# Logica_ADC.net
KiCad netlist of a schematic drawn in Altium Designer
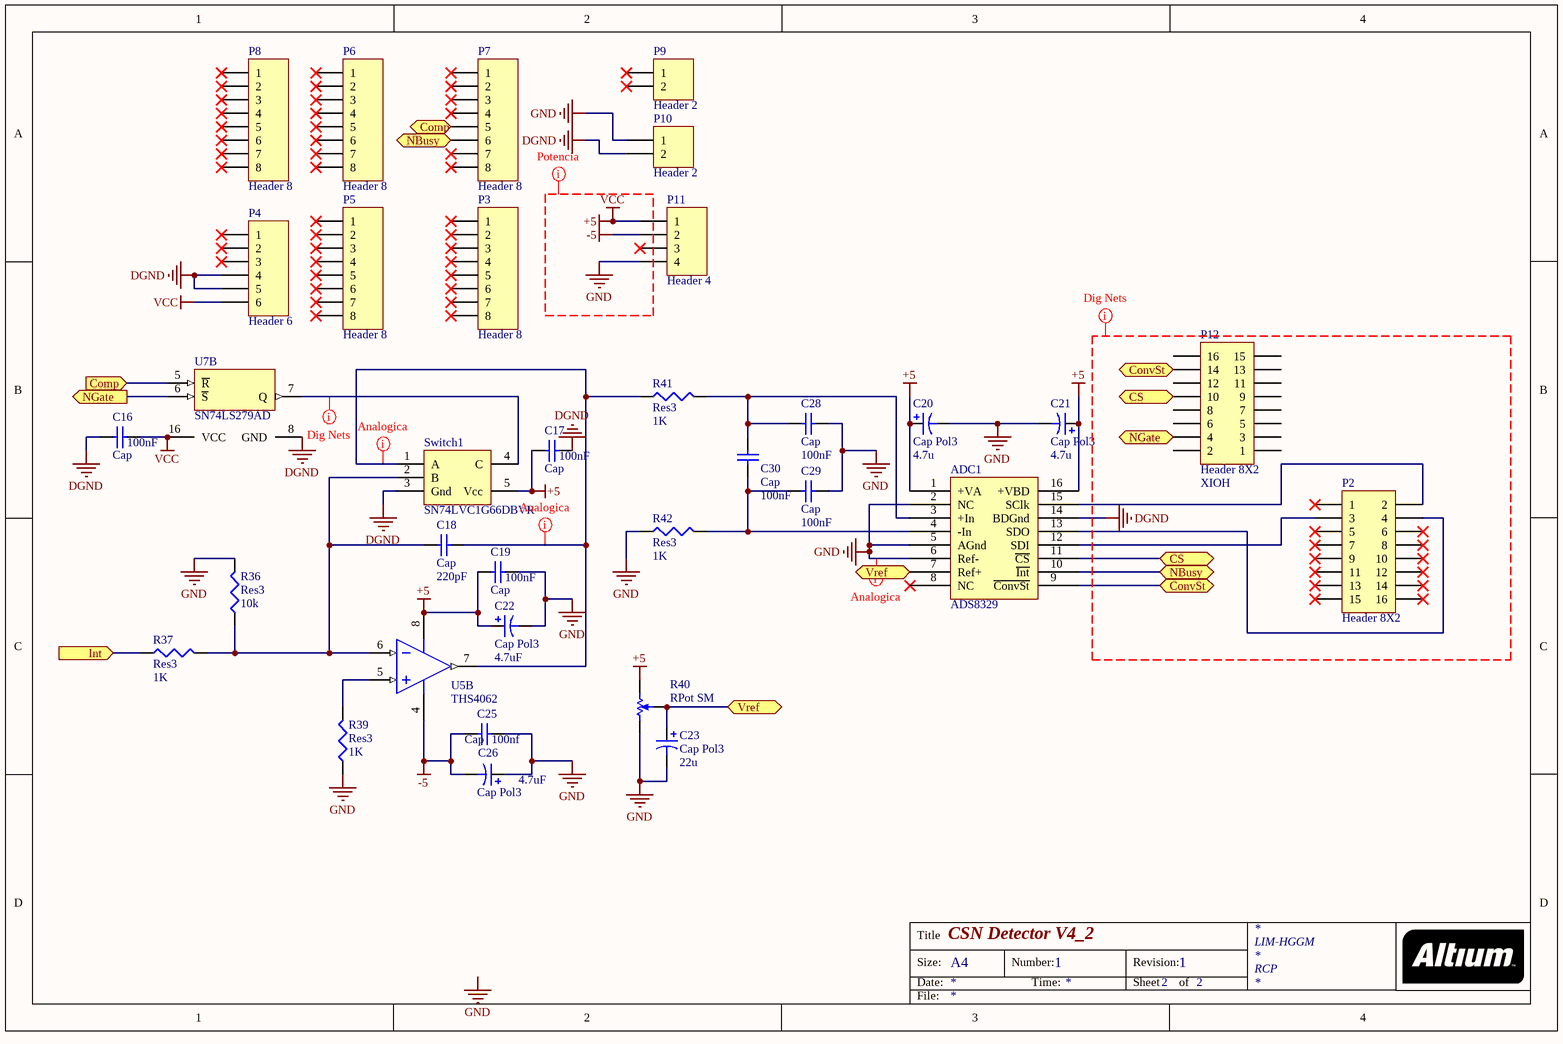
[diagram p0: Logica_ADC.SchDoc]

(export (version "E")
  (design (tool "Eeschema 10.0.6"))
  (components
    (comp (ref "ADC1")
      (value "ADS8329")
      (footprint "PW-R-PDSO-G16")
      (libsource (lib "Int_Lib1") (part "ADS8329"))
    )
    (comp (ref "C16")
      (value "Cap")
      (footprint "6-0805_N")
      (description "Capacitor")
      (fields (field (name "ALTIUM_VALUE") "100nF") (field (name "PUBLISHER") "Altium Limited"))
      (libsource (lib "Miscellaneous Devices") (part "Cap"))
    )
    (comp (ref "C17")
      (value "Cap")
      (footprint "6-0805_N")
      (description "Capacitor")
      (fields (field (name "ALTIUM_VALUE") "100nF") (field (name "PUBLISHER") "Altium Limited"))
      (libsource (lib "Miscellaneous Devices") (part "Cap"))
    )
    (comp (ref "C18")
      (value "Cap")
      (footprint "6-0805_N")
      (description "Capacitor")
      (fields (field (name "ALTIUM_VALUE") "220pF") (field (name "PUBLISHER") "Altium Limited"))
      (libsource (lib "Miscellaneous Devices") (part "Cap"))
    )
    (comp (ref "C19")
      (value "Cap")
      (footprint "6-0805_N")
      (description "Capacitor")
      (fields (field (name "ALTIUM_VALUE") "100nF") (field (name "PUBLISHER") "Altium Limited"))
      (libsource (lib "Miscellaneous Devices") (part "Cap"))
    )
    (comp (ref "C20")
      (value "Cap Pol3")
      (footprint "6-0805_N")
      (description "Polarized Capacitor (Surface Mount)")
      (fields (field (name "ALTIUM_VALUE") "4.7u") (field (name "PUBLISHER") "Altium Limited"))
      (libsource (lib "Miscellaneous Devices") (part "Cap Pol3"))
    )
    (comp (ref "C21")
      (value "Cap Pol3")
      (footprint "6-0805_N")
      (description "Polarized Capacitor (Surface Mount)")
      (fields (field (name "ALTIUM_VALUE") "4.7u") (field (name "PUBLISHER") "Altium Limited"))
      (libsource (lib "Miscellaneous Devices") (part "Cap Pol3"))
    )
    (comp (ref "C22")
      (value "Cap Pol3")
      (footprint "6-0805_N")
      (description "Polarized Capacitor (Surface Mount)")
      (fields (field (name "ALTIUM_VALUE") "4.7uF") (field (name "PUBLISHER") "Altium Limited"))
      (libsource (lib "Miscellaneous Devices") (part "Cap Pol3"))
    )
    (comp (ref "C23")
      (value "Cap Pol3")
      (footprint "6-0805_N")
      (description "Polarized Capacitor (Surface Mount)")
      (fields (field (name "ALTIUM_VALUE") "22u") (field (name "PUBLISHER") "Altium Limited"))
      (libsource (lib "Miscellaneous Devices") (part "Cap Pol3"))
    )
    (comp (ref "C25")
      (value "Cap")
      (footprint "6-0805_N")
      (description "Capacitor")
      (fields (field (name "ALTIUM_VALUE") "100nf") (field (name "PUBLISHER") "Altium Limited"))
      (libsource (lib "Miscellaneous Devices") (part "Cap"))
    )
    (comp (ref "C26")
      (value "Cap Pol3")
      (footprint "6-0805_N")
      (description "Polarized Capacitor (Surface Mount)")
      (fields (field (name "ALTIUM_VALUE") "4.7uF") (field (name "PUBLISHER") "Altium Limited"))
      (libsource (lib "Miscellaneous Devices") (part "Cap Pol3"))
    )
    (comp (ref "C28")
      (value "Cap")
      (footprint "6-0805_N")
      (description "Capacitor")
      (fields (field (name "ALTIUM_VALUE") "100nF") (field (name "PUBLISHER") "Altium Limited"))
      (libsource (lib "Miscellaneous Devices") (part "Cap"))
    )
    (comp (ref "C29")
      (value "Cap")
      (footprint "6-0805_N")
      (description "Capacitor")
      (fields (field (name "ALTIUM_VALUE") "100nF") (field (name "PUBLISHER") "Altium Limited"))
      (libsource (lib "Miscellaneous Devices") (part "Cap"))
    )
    (comp (ref "C30")
      (value "Cap")
      (footprint "6-0805_N")
      (description "Capacitor")
      (fields (field (name "ALTIUM_VALUE") "100nF") (field (name "PUBLISHER") "Altium Limited"))
      (libsource (lib "Miscellaneous Devices") (part "Cap"))
    )
    (comp (ref "P2")
      (value "Header 8X2")
      (footprint "HDR2X8")
      (description "Header, 8-Pin, Dual row")
      (fields (field (name "PUBLISHER") "Altium Limited"))
      (libsource (lib "") (part "Header 8X2_1"))
    )
    (comp (ref "P3")
      (value "Header 8")
      (footprint "HDR1X8")
      (description "Header, 8-Pin")
      (fields (field (name "PUBLISHER") "Altium Limited"))
      (libsource (lib "Miscellaneous Connectors") (part "Header 8"))
    )
    (comp (ref "P4")
      (value "Header 6")
      (footprint "HDR1X6")
      (description "Header, 6-Pin")
      (fields (field (name "PUBLISHER") "Altium Limited"))
      (libsource (lib "Miscellaneous Connectors") (part "Header 6"))
    )
    (comp (ref "P5")
      (value "Header 8")
      (footprint "HDR1X8")
      (description "Header, 8-Pin")
      (fields (field (name "PUBLISHER") "Altium Limited"))
      (libsource (lib "Miscellaneous Connectors") (part "Header 8"))
    )
    (comp (ref "P6")
      (value "Header 8")
      (footprint "HDR1X8")
      (description "Header, 8-Pin")
      (fields (field (name "PUBLISHER") "Altium Limited"))
      (libsource (lib "Miscellaneous Connectors") (part "Header 8"))
    )
    (comp (ref "P7")
      (value "Header 8")
      (footprint "HDR1X8")
      (description "Header, 8-Pin")
      (fields (field (name "PUBLISHER") "Altium Limited"))
      (libsource (lib "Miscellaneous Connectors") (part "Header 8"))
    )
    (comp (ref "P8")
      (value "Header 8")
      (footprint "HDR1X8")
      (description "Header, 8-Pin")
      (fields (field (name "PUBLISHER") "Altium Limited"))
      (libsource (lib "Miscellaneous Connectors") (part "Header 8"))
    )
    (comp (ref "P9")
      (value "Header 2")
      (footprint "HDR1X2")
      (description "Header, 2-Pin")
      (fields (field (name "PUBLISHER") "Altium Limited"))
      (libsource (lib "Miscellaneous Connectors") (part "Header 2"))
    )
    (comp (ref "P10")
      (value "Header 2")
      (footprint "HDR1X2")
      (description "Header, 2-Pin")
      (fields (field (name "PUBLISHER") "Altium Limited"))
      (libsource (lib "Miscellaneous Connectors") (part "Header 2"))
    )
    (comp (ref "P11")
      (value "Header 4")
      (footprint "HDR1X4")
      (description "Header, 4-Pin")
      (fields (field (name "PUBLISHER") "Altium Limited"))
      (libsource (lib "Miscellaneous Connectors") (part "Header 4"))
    )
    (comp (ref "P12")
      (value "Header 8X2")
      (footprint "HDR2X8")
      (description "Header, 8-Pin, Dual row")
      (fields (field (name "CON_ARDUINO") "XIOH") (field (name "PUBLISHER") "Altium Limited"))
      (libsource (lib "Miscellaneous Connectors") (part "Header 8X2"))
    )
    (comp (ref "R36")
      (value "Res3")
      (footprint "6-0805_N")
      (description "Resistor")
      (fields (field (name "ALTIUM_VALUE") "10k") (field (name "PUBLISHER") "Altium Limited"))
      (libsource (lib "Miscellaneous Devices") (part "Res3"))
    )
    (comp (ref "R37")
      (value "Res3")
      (footprint "6-0805_N")
      (description "Resistor")
      (fields (field (name "ALTIUM_VALUE") "1K") (field (name "PUBLISHER") "Altium Limited"))
      (libsource (lib "Miscellaneous Devices") (part "Res3"))
    )
    (comp (ref "R39")
      (value "Res3")
      (footprint "6-0805_N")
      (description "Resistor")
      (fields (field (name "ALTIUM_VALUE") "1K") (field (name "PUBLISHER") "Altium Limited"))
      (libsource (lib "Miscellaneous Devices") (part "Res3"))
    )
    (comp (ref "R40")
      (value "RPot SM")
      (footprint "POT4MM-2")
      (description "Square Trimming Potentiometer")
      (fields (field (name "PUBLISHER") "Altium Limited"))
      (libsource (lib "Miscellaneous Devices") (part "RPot SM"))
    )
    (comp (ref "R41")
      (value "Res3")
      (footprint "6-0805_N")
      (description "Resistor")
      (fields (field (name "ALTIUM_VALUE") "1K") (field (name "PUBLISHER") "Altium Limited"))
      (libsource (lib "Miscellaneous Devices") (part "Res3"))
    )
    (comp (ref "R42")
      (value "Res3")
      (footprint "6-0805_N")
      (description "Resistor")
      (fields (field (name "ALTIUM_VALUE") "1K") (field (name "PUBLISHER") "Altium Limited"))
      (libsource (lib "Miscellaneous Devices") (part "Res3"))
    )
    (comp (ref "Switch1")
      (value "SN74LVC1G66DBVR")
      (footprint "SOT23-5_N")
      (libsource (lib "Integrated_Library1") (part "SN74LVC1G66DBVR"))
    )
    (comp (ref "U5")
      (value "THS4062")
      (footprint "S8_N")
      (description "Low Cost Dual Video Amplifier")
      (fields (field (name "PUBLISHER") "Altium Limited"))
      (libsource (lib "LT Video Amplifier") (part "LT1253CS8"))
    )
    (comp (ref "U7")
      (value "SN74LS279AD")
      (footprint "D016_N")
      (description "Quadruple S-R Latches")
      (fields (field (name "PUBLISHER") "Altium Limited"))
      (libsource (lib "TI Logic Latch") (part "SN74LS279AD"))
    )
  )
  (nets
    (net (code "1") (name "+5") (class "Default")
      (node (ref "ADC1") (pin "1") (pinfunction "+VA_1") (pintype "passive"))
      (node (ref "ADC1") (pin "16") (pinfunction "+VBD_16") (pintype "passive"))
      (node (ref "C16") (pin "1") (pinfunction "1_1") (pintype "passive"))
      (node (ref "C17") (pin "2") (pinfunction "2_2") (pintype "passive"))
      (node (ref "C19") (pin "2") (pinfunction "2_2") (pintype "passive"))
      (node (ref "C20") (pin "1") (pinfunction "1_1") (pintype "passive"))
      (node (ref "C21") (pin "1") (pinfunction "1_1") (pintype "passive"))
      (node (ref "C22") (pin "1") (pinfunction "1_1") (pintype "passive"))
      (node (ref "P11") (pin "1") (pinfunction "1_1") (pintype "passive"))
      (node (ref "P4") (pin "6") (pinfunction "6_6") (pintype "passive"))
      (node (ref "R40") (pin "CW") (pinfunction "+_CW") (pintype "passive"))
      (node (ref "Switch1") (pin "5") (pinfunction "Vcc_5") (pintype "passive"))
      (node (ref "U5") (pin "8") (pinfunction "V+_8") (pintype "power_in"))
      (node (ref "U7") (pin "16") (pinfunction "VCC_16") (pintype "power_in"))
    )
    (net (code "2") (name "-5") (class "Default")
      (node (ref "C25") (pin "1") (pinfunction "1_1") (pintype "passive"))
      (node (ref "C26") (pin "2") (pinfunction "2_2") (pintype "passive"))
      (node (ref "P11") (pin "2") (pinfunction "2_2") (pintype "passive"))
      (node (ref "U5") (pin "4") (pinfunction "V-_4") (pintype "power_in"))
    )
    (net (code "3") (name "/CS") (class "Default")
      (node (ref "ADC1") (pin "11") (pinfunction "~{CS}_11") (pintype "passive"))
      (node (ref "P12") (pin "10") (pinfunction "10_10") (pintype "passive"))
    )
    (net (code "4") (name "/Comp") (class "Default")
      (node (ref "P7") (pin "5") (pinfunction "5_5") (pintype "passive"))
      (node (ref "U7") (pin "5") (pinfunction "~{R}_5") (pintype "input"))
    )
    (net (code "5") (name "/ConvSt") (class "Default")
      (node (ref "ADC1") (pin "9") (pinfunction "~{ConvSt}_9") (pintype "passive"))
      (node (ref "P12") (pin "14") (pinfunction "14_14") (pintype "passive"))
    )
    (net (code "6") (name "/Int") (class "Default")
      (node (ref "R37") (pin "1") (pinfunction "1_1") (pintype "passive"))
    )
    (net (code "7") (name "/NBusy") (class "Default")
      (node (ref "ADC1") (pin "10") (pinfunction "~{Int}_10") (pintype "passive"))
      (node (ref "P7") (pin "6") (pinfunction "6_6") (pintype "passive"))
    )
    (net (code "8") (name "/NGate") (class "Default")
      (node (ref "P12") (pin "4") (pinfunction "4_4") (pintype "passive"))
      (node (ref "U7") (pin "6") (pinfunction "~{S}_6") (pintype "input"))
    )
    (net (code "9") (name "/Vref") (class "Default")
      (node (ref "ADC1") (pin "7") (pinfunction "Ref+_7") (pintype "passive"))
      (node (ref "C23") (pin "1") (pinfunction "1_1") (pintype "passive"))
      (node (ref "R40") (pin "W") (pinfunction "W_W") (pintype "passive"))
    )
    (net (code "10") (name "DGND") (class "Default")
      (node (ref "ADC1") (pin "14") (pinfunction "BDGnd_14") (pintype "passive"))
      (node (ref "ADC1") (pin "2") (pinfunction "NC_2") (pintype "passive"))
      (node (ref "ADC1") (pin "5") (pinfunction "AGnd_5") (pintype "passive"))
      (node (ref "ADC1") (pin "6") (pinfunction "Ref-_6") (pintype "passive"))
      (node (ref "C16") (pin "2") (pinfunction "2_2") (pintype "passive"))
      (node (ref "C17") (pin "1") (pinfunction "1_1") (pintype "passive"))
      (node (ref "C19") (pin "1") (pinfunction "1_1") (pintype "passive"))
      (node (ref "C20") (pin "2") (pinfunction "2_2") (pintype "passive"))
      (node (ref "C21") (pin "2") (pinfunction "2_2") (pintype "passive"))
      (node (ref "C22") (pin "2") (pinfunction "2_2") (pintype "passive"))
      (node (ref "C23") (pin "2") (pinfunction "2_2") (pintype "passive"))
      (node (ref "C25") (pin "2") (pinfunction "2_2") (pintype "passive"))
      (node (ref "C26") (pin "1") (pinfunction "1_1") (pintype "passive"))
      (node (ref "C28") (pin "1") (pinfunction "1_1") (pintype "passive"))
      (node (ref "C29") (pin "1") (pinfunction "1_1") (pintype "passive"))
      (node (ref "P10") (pin "1") (pinfunction "1_1") (pintype "passive"))
      (node (ref "P10") (pin "2") (pinfunction "2_2") (pintype "passive"))
      (node (ref "P11") (pin "4") (pinfunction "4_4") (pintype "passive"))
      (node (ref "P4") (pin "4") (pinfunction "4_4") (pintype "passive"))
      (node (ref "P4") (pin "5") (pinfunction "5_5") (pintype "passive"))
      (node (ref "R36") (pin "2") (pinfunction "2_2") (pintype "passive"))
      (node (ref "R39") (pin "1") (pinfunction "1_1") (pintype "passive"))
      (node (ref "R40") (pin "CCW") (pinfunction "-_CCW") (pintype "passive"))
      (node (ref "R42") (pin "1") (pinfunction "1_1") (pintype "passive"))
      (node (ref "Switch1") (pin "3") (pinfunction "Gnd_3") (pintype "passive"))
      (node (ref "U7") (pin "8") (pinfunction "GND_8") (pintype "power_in"))
    )
    (net (code "11") (name "Net-(ADC1-+In)") (class "Default")
      (node (ref "ADC1") (pin "3") (pinfunction "+In_3") (pintype "passive"))
      (node (ref "C28") (pin "2") (pinfunction "2_2") (pintype "passive"))
      (node (ref "C30") (pin "2") (pinfunction "2_2") (pintype "passive"))
      (node (ref "R41") (pin "2") (pinfunction "2_2") (pintype "passive"))
    )
    (net (code "12") (name "Net-(ADC1--In)") (class "Default")
      (node (ref "ADC1") (pin "4") (pinfunction "-In_4") (pintype "passive"))
      (node (ref "C29") (pin "2") (pinfunction "2_2") (pintype "passive"))
      (node (ref "C30") (pin "1") (pinfunction "1_1") (pintype "passive"))
      (node (ref "R42") (pin "2") (pinfunction "2_2") (pintype "passive"))
    )
    (net (code "13") (name "Net-(ADC1-SClk)") (class "Default")
      (node (ref "ADC1") (pin "15") (pinfunction "SClk_15") (pintype "passive"))
      (node (ref "P2") (pin "2") (pinfunction "2_2") (pintype "passive"))
    )
    (net (code "14") (name "Net-(ADC1-SDI)") (class "Default")
      (node (ref "ADC1") (pin "12") (pinfunction "SDI_12") (pintype "passive"))
      (node (ref "P2") (pin "3") (pinfunction "3_3") (pintype "passive"))
    )
    (net (code "15") (name "Net-(ADC1-SDO)") (class "Default")
      (node (ref "ADC1") (pin "13") (pinfunction "SDO_13") (pintype "passive"))
      (node (ref "P2") (pin "4") (pinfunction "4_4") (pintype "passive"))
    )
    (net (code "16") (name "Net-(Switch1-A)") (class "Default")
      (node (ref "C18") (pin "2") (pinfunction "2_2") (pintype "passive"))
      (node (ref "R41") (pin "1") (pinfunction "1_1") (pintype "passive"))
      (node (ref "Switch1") (pin "1") (pinfunction "A_1") (pintype "passive"))
      (node (ref "U5") (pin "7") (pinfunction "OUT_7") (pintype "output"))
    )
    (net (code "17") (name "Net-(Switch1-B)") (class "Default")
      (node (ref "C18") (pin "1") (pinfunction "1_1") (pintype "passive"))
      (node (ref "R36") (pin "1") (pinfunction "1_1") (pintype "passive"))
      (node (ref "R37") (pin "2") (pinfunction "2_2") (pintype "passive"))
      (node (ref "Switch1") (pin "2") (pinfunction "B_2") (pintype "passive"))
      (node (ref "U5") (pin "6") (pinfunction "IN-_6") (pintype "input"))
    )
    (net (code "18") (name "Net-(Switch1-C)") (class "Default")
      (node (ref "Switch1") (pin "4") (pinfunction "C_4") (pintype "passive"))
      (node (ref "U7") (pin "7") (pinfunction "Q_7") (pintype "output"))
    )
    (net (code "19") (name "Net-(U5B-IN+)") (class "Default")
      (node (ref "R39") (pin "2") (pinfunction "2_2") (pintype "passive"))
      (node (ref "U5") (pin "5") (pinfunction "IN+_5") (pintype "input"))
    )
    (net (code "20") (name "unconnected-(ADC1-NC-Pad8)") (class "Default")
      (node (ref "ADC1") (pin "8") (pinfunction "NC_8") (pintype "passive+no_connect"))
    )
    (net (code "21") (name "unconnected-(P2-Pad1)") (class "Default")
      (node (ref "P2") (pin "1") (pinfunction "1_1") (pintype "passive+no_connect"))
    )
    (net (code "22") (name "unconnected-(P2-Pad5)") (class "Default")
      (node (ref "P2") (pin "5") (pinfunction "5_5") (pintype "passive+no_connect"))
    )
    (net (code "23") (name "unconnected-(P2-Pad6)") (class "Default")
      (node (ref "P2") (pin "6") (pinfunction "6_6") (pintype "passive+no_connect"))
    )
    (net (code "24") (name "unconnected-(P2-Pad7)") (class "Default")
      (node (ref "P2") (pin "7") (pinfunction "7_7") (pintype "passive+no_connect"))
    )
    (net (code "25") (name "unconnected-(P2-Pad8)") (class "Default")
      (node (ref "P2") (pin "8") (pinfunction "8_8") (pintype "passive+no_connect"))
    )
    (net (code "26") (name "unconnected-(P2-Pad9)") (class "Default")
      (node (ref "P2") (pin "9") (pinfunction "9_9") (pintype "passive+no_connect"))
    )
    (net (code "27") (name "unconnected-(P2-Pad10)") (class "Default")
      (node (ref "P2") (pin "10") (pinfunction "10_10") (pintype "passive+no_connect"))
    )
    (net (code "28") (name "unconnected-(P2-Pad11)") (class "Default")
      (node (ref "P2") (pin "11") (pinfunction "11_11") (pintype "passive+no_connect"))
    )
    (net (code "29") (name "unconnected-(P2-Pad12)") (class "Default")
      (node (ref "P2") (pin "12") (pinfunction "12_12") (pintype "passive+no_connect"))
    )
    (net (code "30") (name "unconnected-(P2-Pad13)") (class "Default")
      (node (ref "P2") (pin "13") (pinfunction "13_13") (pintype "passive+no_connect"))
    )
    (net (code "31") (name "unconnected-(P2-Pad14)") (class "Default")
      (node (ref "P2") (pin "14") (pinfunction "14_14") (pintype "passive+no_connect"))
    )
    (net (code "32") (name "unconnected-(P2-Pad15)") (class "Default")
      (node (ref "P2") (pin "15") (pinfunction "15_15") (pintype "passive+no_connect"))
    )
    (net (code "33") (name "unconnected-(P2-Pad16)") (class "Default")
      (node (ref "P2") (pin "16") (pinfunction "16_16") (pintype "passive+no_connect"))
    )
    (net (code "34") (name "unconnected-(P3-Pad1)") (class "Default")
      (node (ref "P3") (pin "1") (pinfunction "1_1") (pintype "passive+no_connect"))
    )
    (net (code "35") (name "unconnected-(P3-Pad2)") (class "Default")
      (node (ref "P3") (pin "2") (pinfunction "2_2") (pintype "passive+no_connect"))
    )
    (net (code "36") (name "unconnected-(P3-Pad3)") (class "Default")
      (node (ref "P3") (pin "3") (pinfunction "3_3") (pintype "passive+no_connect"))
    )
    (net (code "37") (name "unconnected-(P3-Pad4)") (class "Default")
      (node (ref "P3") (pin "4") (pinfunction "4_4") (pintype "passive+no_connect"))
    )
    (net (code "38") (name "unconnected-(P3-Pad5)") (class "Default")
      (node (ref "P3") (pin "5") (pinfunction "5_5") (pintype "passive+no_connect"))
    )
    (net (code "39") (name "unconnected-(P3-Pad6)") (class "Default")
      (node (ref "P3") (pin "6") (pinfunction "6_6") (pintype "passive+no_connect"))
    )
    (net (code "40") (name "unconnected-(P3-Pad7)") (class "Default")
      (node (ref "P3") (pin "7") (pinfunction "7_7") (pintype "passive+no_connect"))
    )
    (net (code "41") (name "unconnected-(P3-Pad8)") (class "Default")
      (node (ref "P3") (pin "8") (pinfunction "8_8") (pintype "passive+no_connect"))
    )
    (net (code "42") (name "unconnected-(P4-Pad1)") (class "Default")
      (node (ref "P4") (pin "1") (pinfunction "1_1") (pintype "passive+no_connect"))
    )
    (net (code "43") (name "unconnected-(P4-Pad2)") (class "Default")
      (node (ref "P4") (pin "2") (pinfunction "2_2") (pintype "passive+no_connect"))
    )
    (net (code "44") (name "unconnected-(P4-Pad3)") (class "Default")
      (node (ref "P4") (pin "3") (pinfunction "3_3") (pintype "passive+no_connect"))
    )
    (net (code "45") (name "unconnected-(P5-Pad1)") (class "Default")
      (node (ref "P5") (pin "1") (pinfunction "1_1") (pintype "passive+no_connect"))
    )
    (net (code "46") (name "unconnected-(P5-Pad2)") (class "Default")
      (node (ref "P5") (pin "2") (pinfunction "2_2") (pintype "passive+no_connect"))
    )
    (net (code "47") (name "unconnected-(P5-Pad3)") (class "Default")
      (node (ref "P5") (pin "3") (pinfunction "3_3") (pintype "passive+no_connect"))
    )
    (net (code "48") (name "unconnected-(P5-Pad4)") (class "Default")
      (node (ref "P5") (pin "4") (pinfunction "4_4") (pintype "passive+no_connect"))
    )
    (net (code "49") (name "unconnected-(P5-Pad5)") (class "Default")
      (node (ref "P5") (pin "5") (pinfunction "5_5") (pintype "passive+no_connect"))
    )
    (net (code "50") (name "unconnected-(P5-Pad6)") (class "Default")
      (node (ref "P5") (pin "6") (pinfunction "6_6") (pintype "passive+no_connect"))
    )
    (net (code "51") (name "unconnected-(P5-Pad7)") (class "Default")
      (node (ref "P5") (pin "7") (pinfunction "7_7") (pintype "passive+no_connect"))
    )
    (net (code "52") (name "unconnected-(P5-Pad8)") (class "Default")
      (node (ref "P5") (pin "8") (pinfunction "8_8") (pintype "passive+no_connect"))
    )
    (net (code "53") (name "unconnected-(P6-Pad1)") (class "Default")
      (node (ref "P6") (pin "1") (pinfunction "1_1") (pintype "passive+no_connect"))
    )
    (net (code "54") (name "unconnected-(P6-Pad2)") (class "Default")
      (node (ref "P6") (pin "2") (pinfunction "2_2") (pintype "passive+no_connect"))
    )
    (net (code "55") (name "unconnected-(P6-Pad3)") (class "Default")
      (node (ref "P6") (pin "3") (pinfunction "3_3") (pintype "passive+no_connect"))
    )
    (net (code "56") (name "unconnected-(P6-Pad4)") (class "Default")
      (node (ref "P6") (pin "4") (pinfunction "4_4") (pintype "passive+no_connect"))
    )
    (net (code "57") (name "unconnected-(P6-Pad5)") (class "Default")
      (node (ref "P6") (pin "5") (pinfunction "5_5") (pintype "passive+no_connect"))
    )
    (net (code "58") (name "unconnected-(P6-Pad6)") (class "Default")
      (node (ref "P6") (pin "6") (pinfunction "6_6") (pintype "passive+no_connect"))
    )
    (net (code "59") (name "unconnected-(P6-Pad7)") (class "Default")
      (node (ref "P6") (pin "7") (pinfunction "7_7") (pintype "passive+no_connect"))
    )
    (net (code "60") (name "unconnected-(P6-Pad8)") (class "Default")
      (node (ref "P6") (pin "8") (pinfunction "8_8") (pintype "passive+no_connect"))
    )
    (net (code "61") (name "unconnected-(P7-Pad1)") (class "Default")
      (node (ref "P7") (pin "1") (pinfunction "1_1") (pintype "passive+no_connect"))
    )
    (net (code "62") (name "unconnected-(P7-Pad2)") (class "Default")
      (node (ref "P7") (pin "2") (pinfunction "2_2") (pintype "passive+no_connect"))
    )
    (net (code "63") (name "unconnected-(P7-Pad3)") (class "Default")
      (node (ref "P7") (pin "3") (pinfunction "3_3") (pintype "passive+no_connect"))
    )
    (net (code "64") (name "unconnected-(P7-Pad4)") (class "Default")
      (node (ref "P7") (pin "4") (pinfunction "4_4") (pintype "passive+no_connect"))
    )
    (net (code "65") (name "unconnected-(P7-Pad7)") (class "Default")
      (node (ref "P7") (pin "7") (pinfunction "7_7") (pintype "passive+no_connect"))
    )
    (net (code "66") (name "unconnected-(P7-Pad8)") (class "Default")
      (node (ref "P7") (pin "8") (pinfunction "8_8") (pintype "passive+no_connect"))
    )
    (net (code "67") (name "unconnected-(P8-Pad1)") (class "Default")
      (node (ref "P8") (pin "1") (pinfunction "1_1") (pintype "passive+no_connect"))
    )
    (net (code "68") (name "unconnected-(P8-Pad2)") (class "Default")
      (node (ref "P8") (pin "2") (pinfunction "2_2") (pintype "passive+no_connect"))
    )
    (net (code "69") (name "unconnected-(P8-Pad3)") (class "Default")
      (node (ref "P8") (pin "3") (pinfunction "3_3") (pintype "passive+no_connect"))
    )
    (net (code "70") (name "unconnected-(P8-Pad4)") (class "Default")
      (node (ref "P8") (pin "4") (pinfunction "4_4") (pintype "passive+no_connect"))
    )
    (net (code "71") (name "unconnected-(P8-Pad5)") (class "Default")
      (node (ref "P8") (pin "5") (pinfunction "5_5") (pintype "passive+no_connect"))
    )
    (net (code "72") (name "unconnected-(P8-Pad6)") (class "Default")
      (node (ref "P8") (pin "6") (pinfunction "6_6") (pintype "passive+no_connect"))
    )
    (net (code "73") (name "unconnected-(P8-Pad7)") (class "Default")
      (node (ref "P8") (pin "7") (pinfunction "7_7") (pintype "passive+no_connect"))
    )
    (net (code "74") (name "unconnected-(P8-Pad8)") (class "Default")
      (node (ref "P8") (pin "8") (pinfunction "8_8") (pintype "passive+no_connect"))
    )
    (net (code "75") (name "unconnected-(P9-Pad1)") (class "Default")
      (node (ref "P9") (pin "1") (pinfunction "1_1") (pintype "passive+no_connect"))
    )
    (net (code "76") (name "unconnected-(P9-Pad2)") (class "Default")
      (node (ref "P9") (pin "2") (pinfunction "2_2") (pintype "passive+no_connect"))
    )
    (net (code "77") (name "unconnected-(P11-Pad3)") (class "Default")
      (node (ref "P11") (pin "3") (pinfunction "3_3") (pintype "passive+no_connect"))
    )
    (net (code "78") (name "unconnected-(P12-Pad1)") (class "Default")
      (node (ref "P12") (pin "1") (pinfunction "1_1") (pintype "passive"))
    )
    (net (code "79") (name "unconnected-(P12-Pad2)") (class "Default")
      (node (ref "P12") (pin "2") (pinfunction "2_2") (pintype "passive"))
    )
    (net (code "80") (name "unconnected-(P12-Pad3)") (class "Default")
      (node (ref "P12") (pin "3") (pinfunction "3_3") (pintype "passive"))
    )
    (net (code "81") (name "unconnected-(P12-Pad5)") (class "Default")
      (node (ref "P12") (pin "5") (pinfunction "5_5") (pintype "passive"))
    )
    (net (code "82") (name "unconnected-(P12-Pad6)") (class "Default")
      (node (ref "P12") (pin "6") (pinfunction "6_6") (pintype "passive"))
    )
    (net (code "83") (name "unconnected-(P12-Pad7)") (class "Default")
      (node (ref "P12") (pin "7") (pinfunction "7_7") (pintype "passive"))
    )
    (net (code "84") (name "unconnected-(P12-Pad8)") (class "Default")
      (node (ref "P12") (pin "8") (pinfunction "8_8") (pintype "passive"))
    )
    (net (code "85") (name "unconnected-(P12-Pad9)") (class "Default")
      (node (ref "P12") (pin "9") (pinfunction "9_9") (pintype "passive"))
    )
    (net (code "86") (name "unconnected-(P12-Pad11)") (class "Default")
      (node (ref "P12") (pin "11") (pinfunction "11_11") (pintype "passive"))
    )
    (net (code "87") (name "unconnected-(P12-Pad12)") (class "Default")
      (node (ref "P12") (pin "12") (pinfunction "12_12") (pintype "passive"))
    )
    (net (code "88") (name "unconnected-(P12-Pad13)") (class "Default")
      (node (ref "P12") (pin "13") (pinfunction "13_13") (pintype "passive"))
    )
    (net (code "89") (name "unconnected-(P12-Pad15)") (class "Default")
      (node (ref "P12") (pin "15") (pinfunction "15_15") (pintype "passive"))
    )
    (net (code "90") (name "unconnected-(P12-Pad16)") (class "Default")
      (node (ref "P12") (pin "16") (pinfunction "16_16") (pintype "passive"))
    )
  )
)
